# Relays.net
KiCad netlist of a schematic drawn in EAGLE
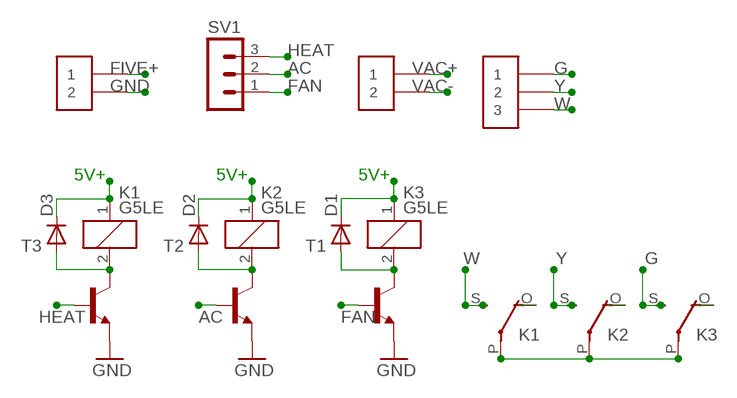
[diagram p0: schematic, sheet 1]

(export (version "E")
  (design (tool "Eeschema 10.0.6"))
  (components
    (comp (ref "D1")
      (value "1N4148DO35-7")
      (footprint "eagle-import:DO35-7")
      (libsource (lib "eagle-import") (part "1N4148DO35-7"))
    )
    (comp (ref "D2")
      (value "1N4148DO35-7")
      (footprint "eagle-import:DO35-7")
      (libsource (lib "eagle-import") (part "1N4148DO35-7"))
    )
    (comp (ref "D3")
      (value "1N4148DO35-7")
      (footprint "eagle-import:DO35-7")
      (libsource (lib "eagle-import") (part "1N4148DO35-7"))
    )
    (comp (ref "K1")
      (value "G5LE")
      (footprint "eagle-import:G5LE")
      (libsource (lib "eagle-import") (part "G5LE"))
    )
    (comp (ref "K2")
      (value "G5LE")
      (footprint "eagle-import:G5LE")
      (libsource (lib "eagle-import") (part "G5LE"))
    )
    (comp (ref "K3")
      (value "G5LE")
      (footprint "eagle-import:G5LE")
      (libsource (lib "eagle-import") (part "G5LE"))
    )
    (comp (ref "SV1")
      (value "MA03-1")
      (footprint "eagle-import:MA03-1")
      (libsource (lib "eagle-import") (part "MA03-1"))
    )
    (comp (ref "T1")
      (value "2N4401-NPN-TO92-EBC")
      (footprint "eagle-import:TO92-EBC")
      (libsource (lib "eagle-import") (part "-NPN-TO92-EBC2N4401"))
    )
    (comp (ref "T2")
      (value "2N4401-NPN-TO92-EBC")
      (footprint "eagle-import:TO92-EBC")
      (libsource (lib "eagle-import") (part "-NPN-TO92-EBC2N4401"))
    )
    (comp (ref "T3")
      (value "2N4401-NPN-TO92-EBC")
      (footprint "eagle-import:TO92-EBC")
      (libsource (lib "eagle-import") (part "-NPN-TO92-EBC2N4401"))
    )
    (comp (ref "U$4")
      (value "OSTTC020162")
      (footprint "eagle-import:OSTTC020162")
      (libsource (lib "eagle-import") (part "OSTTC020162"))
    )
    (comp (ref "U$5")
      (value "OSTTC020162")
      (footprint "eagle-import:OSTTC020162")
      (libsource (lib "eagle-import") (part "OSTTC020162"))
    )
    (comp (ref "U$6")
      (value "OSTTC030162")
      (footprint "eagle-import:OSTTC030162")
      (libsource (lib "eagle-import") (part "OSTTC030162"))
    )
  )
  (nets
    (net (code "1") (name "/AC") (class "Default")
      (node (ref "SV1") (pin "2") (pinfunction "2_2") (pintype "passive"))
      (node (ref "T2") (pin "B") (pinfunction "B_B") (pintype "passive"))
    )
    (net (code "2") (name "/FAN") (class "Default")
      (node (ref "SV1") (pin "1") (pinfunction "1_1") (pintype "passive"))
      (node (ref "T1") (pin "B") (pinfunction "B_B") (pintype "passive"))
    )
    (net (code "3") (name "/FIVE+") (class "Default")
      (node (ref "D1") (pin "C") (pinfunction "C_C") (pintype "passive"))
      (node (ref "D2") (pin "C") (pinfunction "C_C") (pintype "passive"))
      (node (ref "D3") (pin "C") (pinfunction "C_C") (pintype "passive"))
      (node (ref "K1") (pin "1") (pinfunction "1_1") (pintype "passive"))
      (node (ref "K2") (pin "1") (pinfunction "1_1") (pintype "passive"))
      (node (ref "K3") (pin "1") (pinfunction "1_1") (pintype "passive"))
      (node (ref "U$5") (pin "1") (pinfunction "1_1") (pintype "bidirectional"))
    )
    (net (code "4") (name "/G") (class "Default")
      (node (ref "K3") (pin "S") (pinfunction "S_S") (pintype "passive"))
      (node (ref "U$6") (pin "1") (pinfunction "1_1") (pintype "bidirectional"))
    )
    (net (code "5") (name "/HEAT") (class "Default")
      (node (ref "SV1") (pin "3") (pinfunction "3_3") (pintype "passive"))
      (node (ref "T3") (pin "B") (pinfunction "B_B") (pintype "passive"))
    )
    (net (code "6") (name "/VAC+") (class "Default")
      (node (ref "K1") (pin "P") (pinfunction "P_P") (pintype "passive"))
      (node (ref "K2") (pin "P") (pinfunction "P_P") (pintype "passive"))
      (node (ref "K3") (pin "P") (pinfunction "P_P") (pintype "passive"))
      (node (ref "U$4") (pin "1") (pinfunction "1_1") (pintype "bidirectional"))
    )
    (net (code "7") (name "/VAC-") (class "Default")
      (node (ref "U$4") (pin "2") (pinfunction "2_2") (pintype "bidirectional"))
    )
    (net (code "8") (name "/W") (class "Default")
      (node (ref "K1") (pin "S") (pinfunction "S_S") (pintype "passive"))
      (node (ref "U$6") (pin "3") (pinfunction "3_3") (pintype "bidirectional"))
    )
    (net (code "9") (name "/Y") (class "Default")
      (node (ref "K2") (pin "S") (pinfunction "S_S") (pintype "passive"))
      (node (ref "U$6") (pin "2") (pinfunction "2_2") (pintype "bidirectional"))
    )
    (net (code "10") (name "GND") (class "Default")
      (node (ref "T1") (pin "E") (pinfunction "E_E") (pintype "passive"))
      (node (ref "T2") (pin "E") (pinfunction "E_E") (pintype "passive"))
      (node (ref "T3") (pin "E") (pinfunction "E_E") (pintype "passive"))
      (node (ref "U$5") (pin "2") (pinfunction "2_2") (pintype "bidirectional"))
    )
    (net (code "11") (name "Net-(D1-PadA)") (class "Default")
      (node (ref "D1") (pin "A") (pinfunction "A_A") (pintype "passive"))
      (node (ref "K3") (pin "2") (pinfunction "2_2") (pintype "passive"))
      (node (ref "T1") (pin "C") (pinfunction "C_C") (pintype "passive"))
    )
    (net (code "12") (name "Net-(D2-PadA)") (class "Default")
      (node (ref "D2") (pin "A") (pinfunction "A_A") (pintype "passive"))
      (node (ref "K2") (pin "2") (pinfunction "2_2") (pintype "passive"))
      (node (ref "T2") (pin "C") (pinfunction "C_C") (pintype "passive"))
    )
    (net (code "13") (name "Net-(D3-PadA)") (class "Default")
      (node (ref "D3") (pin "A") (pinfunction "A_A") (pintype "passive"))
      (node (ref "K1") (pin "2") (pinfunction "2_2") (pintype "passive"))
      (node (ref "T3") (pin "C") (pinfunction "C_C") (pintype "passive"))
    )
    (net (code "14") (name "unconnected-(K1-PadO)") (class "Default")
      (node (ref "K1") (pin "O") (pinfunction "O_O") (pintype "passive"))
    )
    (net (code "15") (name "unconnected-(K2-PadO)") (class "Default")
      (node (ref "K2") (pin "O") (pinfunction "O_O") (pintype "passive"))
    )
    (net (code "16") (name "unconnected-(K3-PadO)") (class "Default")
      (node (ref "K3") (pin "O") (pinfunction "O_O") (pintype "passive"))
    )
  )
)
